# Signals.net
KiCad netlist of a schematic drawn in Altium Designer
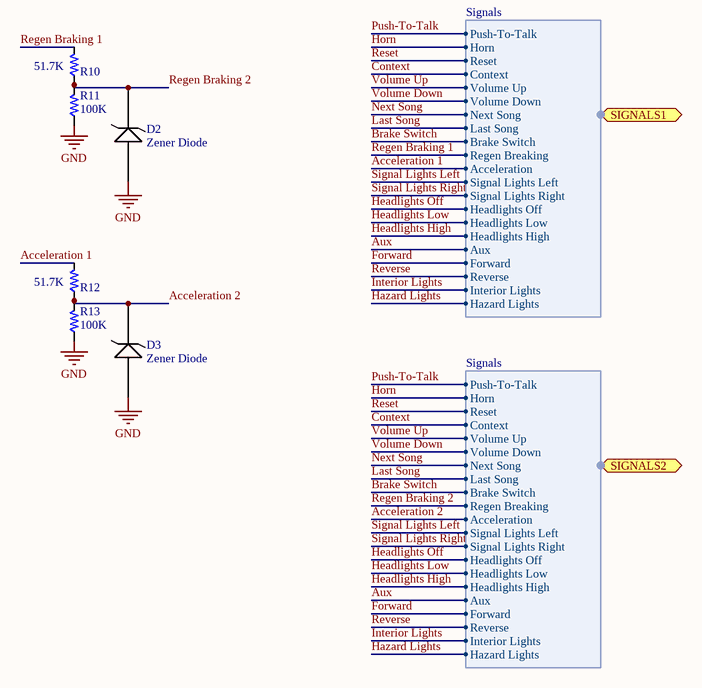
[diagram p0: Signals.SchDoc]

(export (version "E")
  (design (tool "Eeschema 10.0.6"))
  (components
    (comp (ref "D2")
      (value "Zener Diode")
      (footprint "PCBComponent_1")
      (libsource (lib "ZenerDiode") (part "ON Semi Schottky Diode - MBRM110LT1G"))
    )
    (comp (ref "D3")
      (value "Zener Diode")
      (footprint "PCBComponent_1")
      (libsource (lib "ZenerDiode") (part "ON Semi Schottky Diode - MBRM110LT1G"))
    )
    (comp (ref "R10")
      (value "SCH_GENERIC_RESISTOR_0603")
      (footprint "PCB_GENERIC_SMD_0603")
      (description "Generic SMD resistor 0603")
      (fields (field (name "RESISTANCE") "51.7K"))
      (libsource (lib "Generic 0603 Resistor") (part "SCH_GENERIC_RESISTOR_0603"))
    )
    (comp (ref "R11")
      (value "100K")
      (footprint "PCB_GENERIC_SMD_0603")
      (description "RES 0603 100K 5% 63mW")
      (fields (field (name "TOLERANCE") "5%") (field (name "POWER") "63mW"))
      (libsource (lib "RES-0603") (part "R060-00104-05"))
    )
    (comp (ref "R12")
      (value "SCH_GENERIC_RESISTOR_0603")
      (footprint "PCB_GENERIC_SMD_0603")
      (description "Generic SMD resistor 0603")
      (fields (field (name "RESISTANCE") "51.7K"))
      (libsource (lib "Generic 0603 Resistor") (part "SCH_GENERIC_RESISTOR_0603"))
    )
    (comp (ref "R13")
      (value "100K")
      (footprint "PCB_GENERIC_SMD_0603")
      (description "RES 0603 100K 5% 63mW")
      (fields (field (name "TOLERANCE") "5%") (field (name "POWER") "63mW"))
      (libsource (lib "RES-0603") (part "R060-00104-05"))
    )
  )
  (nets
    (net (code "2") (name "/Acceleration 1") (class "Default")
      (node (ref "R12") (pin "2") (pinfunction "2_2") (pintype "passive"))
    )
    (net (code "3") (name "/Acceleration 2") (class "Default")
      (node (ref "D3") (pin "1") (pinfunction "1_1") (pintype "passive"))
      (node (ref "R12") (pin "1") (pinfunction "1_1") (pintype "passive"))
      (node (ref "R13") (pin "2") (pinfunction "2_2") (pintype "passive"))
    )
    (net (code "17") (name "/Regen Braking 1") (class "Default")
      (node (ref "R10") (pin "2") (pinfunction "2_2") (pintype "passive"))
    )
    (net (code "18") (name "/Regen Braking 2") (class "Default")
      (node (ref "D2") (pin "1") (pinfunction "1_1") (pintype "passive"))
      (node (ref "R10") (pin "1") (pinfunction "1_1") (pintype "passive"))
      (node (ref "R11") (pin "2") (pinfunction "2_2") (pintype "passive"))
    )
    (net (code "26") (name "GND") (class "Default")
      (node (ref "D2") (pin "2") (pinfunction "2_2") (pintype "passive"))
      (node (ref "D3") (pin "2") (pinfunction "2_2") (pintype "passive"))
    )
    (net (code "27") (name "unconnected-(R11-Pad1)") (class "Default")
      (node (ref "R11") (pin "1") (pinfunction "1_1") (pintype "passive"))
    )
    (net (code "28") (name "unconnected-(R13-Pad1)") (class "Default")
      (node (ref "R13") (pin "1") (pinfunction "1_1") (pintype "passive"))
    )
  )
)
